# tinyPipes_v2_6.net
KiCad netlist of a schematic drawn in EAGLE
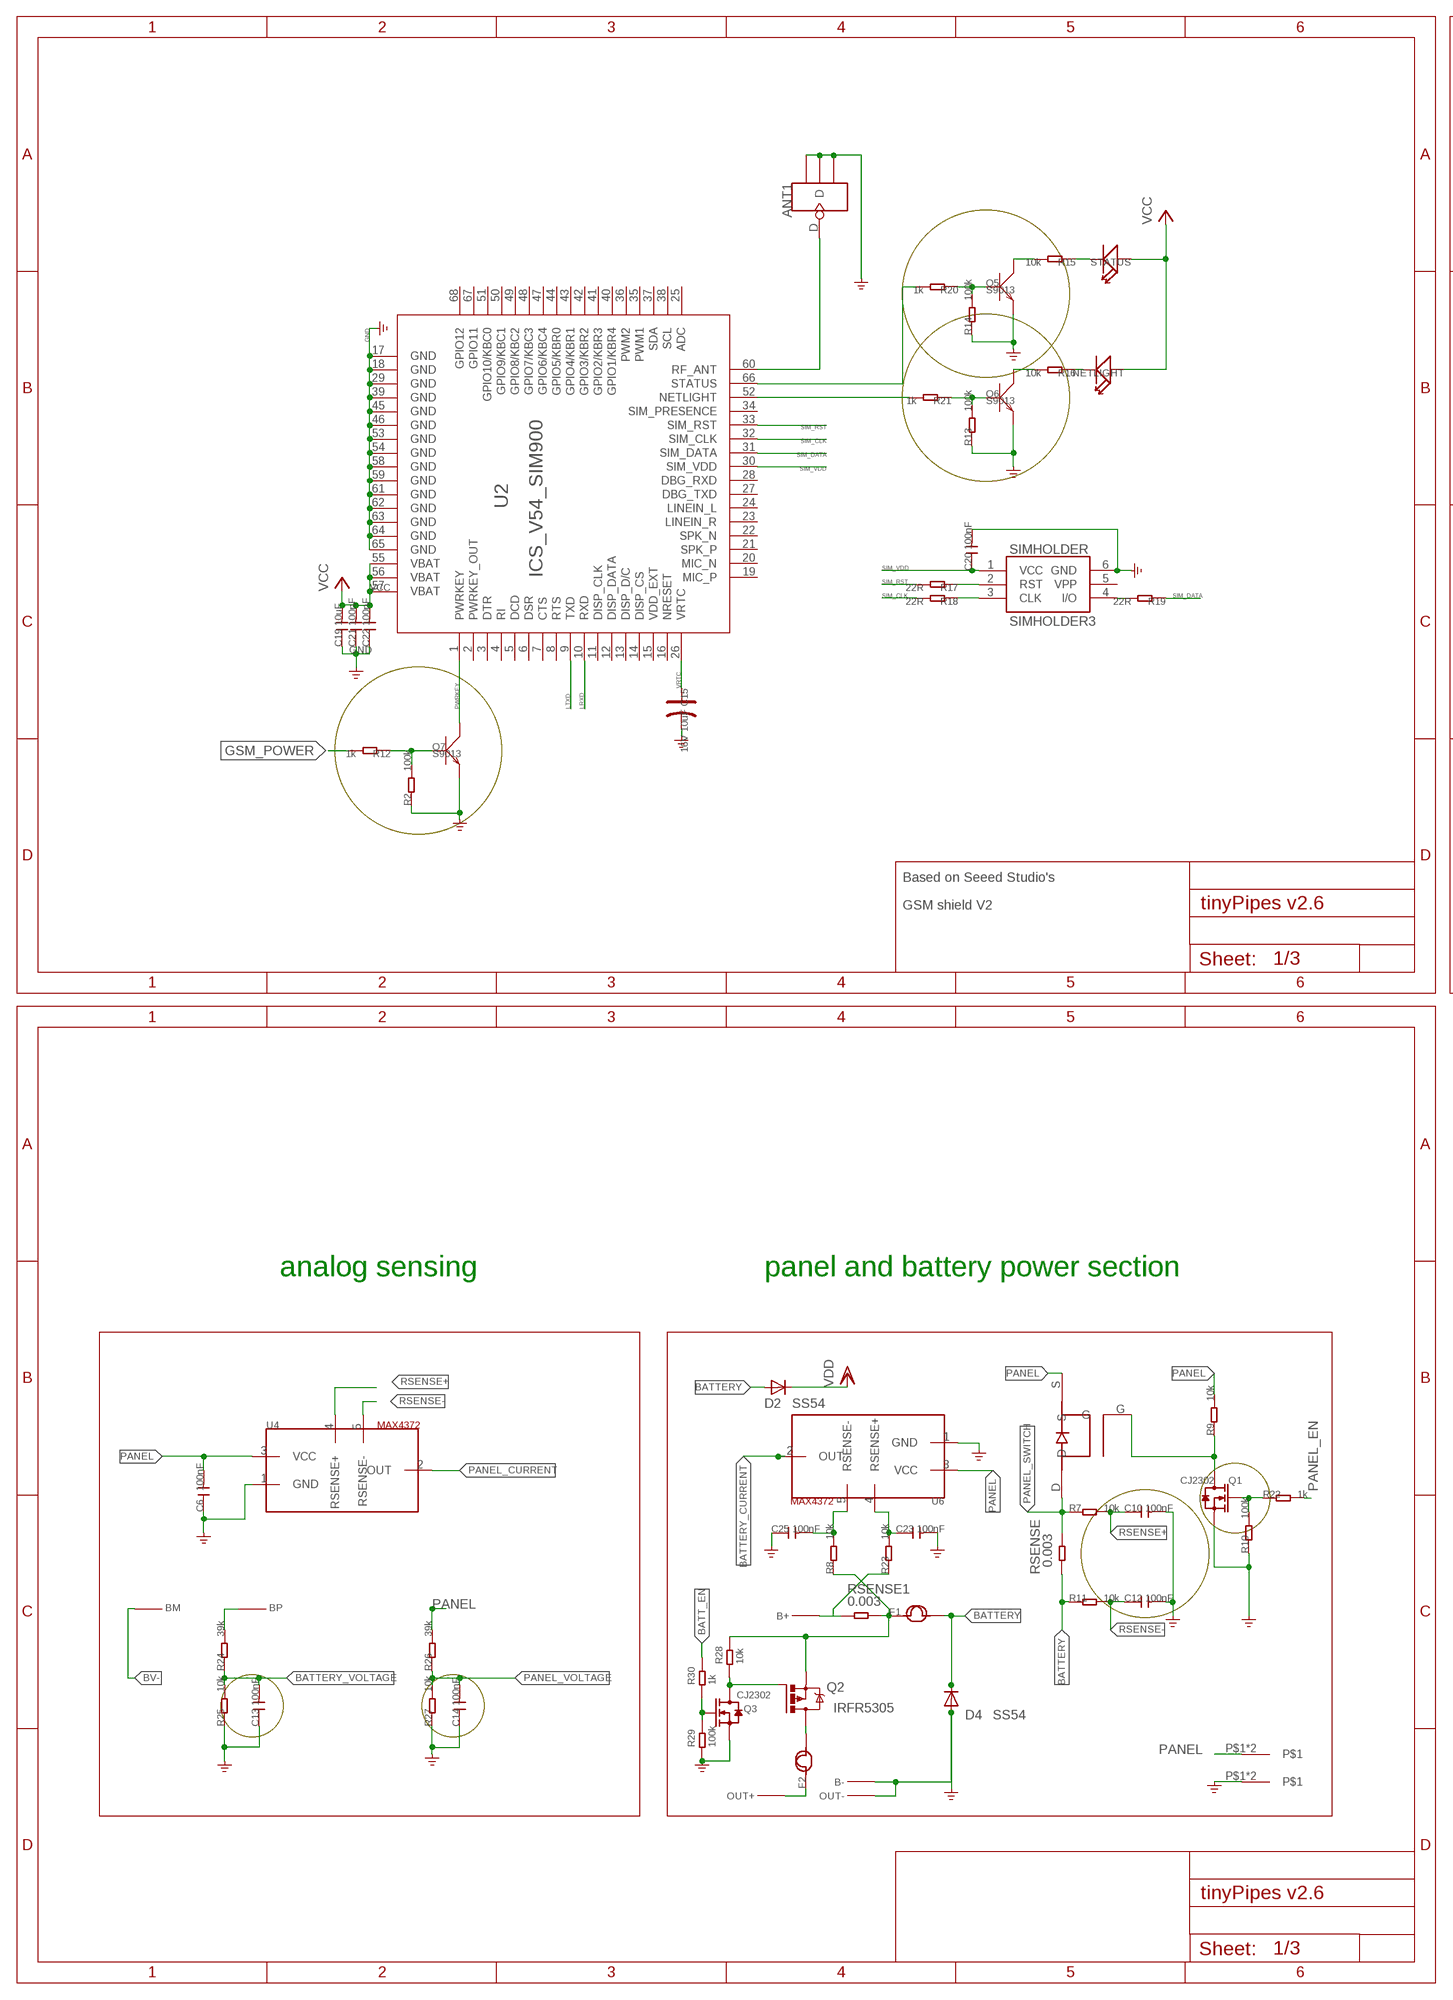
[diagram p0: schematic, sheet 1, part 1 of 2]
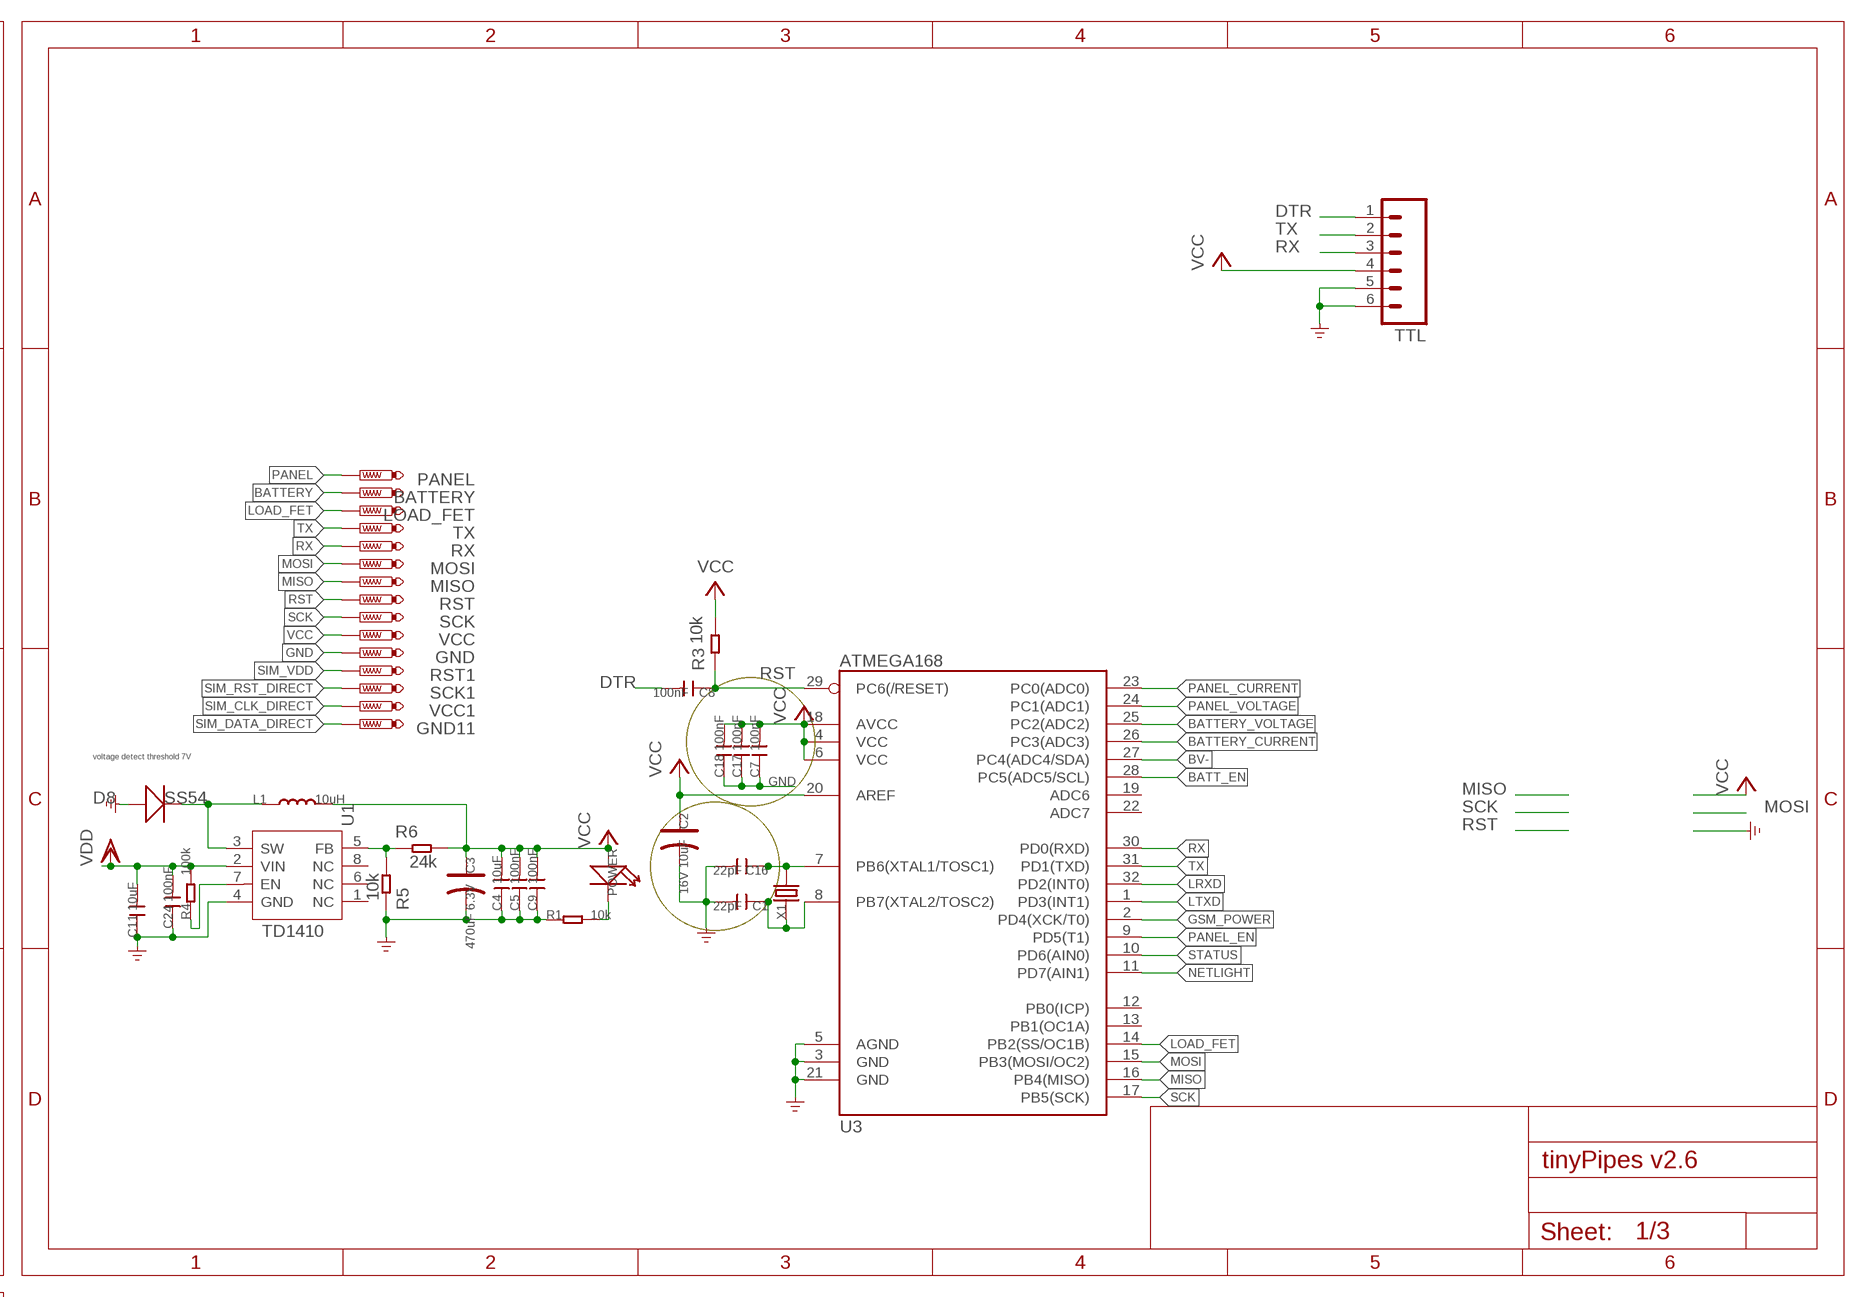
[diagram p1: schematic, sheet 1, part 2 of 2]

(export (version "E")
  (design (tool "Eeschema 10.0.6"))
  (components
    (comp (ref "ANT1")
      (value "ANTENNA-U-FL")
      (footprint "eagle-import:4P-U-FL")
      (libsource (lib "eagle-import") (part "ANTENNA-U-FL"))
    )
    (comp (ref "B+")
      (value "TINYPIPES_BATTBATT")
      (footprint "eagle-import:TINYPIPES_BATT")
      (libsource (lib "eagle-import") (part "TINYPIPES_BATTBATT"))
    )
    (comp (ref "B-")
      (value "TINYPIPES_BATTBATT")
      (footprint "eagle-import:TINYPIPES_BATT")
      (libsource (lib "eagle-import") (part "TINYPIPES_BATTBATT"))
    )
    (comp (ref "BATTERY")
      (value "PTR1B2,54")
      (footprint "eagle-import:B2,54")
      (libsource (lib "eagle-import") (part "PTR1B2,54"))
    )
    (comp (ref "BM")
      (value "TINYPIPES_BATTSBATT")
      (footprint "eagle-import:TINYPIPES_SBATT")
      (libsource (lib "eagle-import") (part "TINYPIPES_BATTSBATT"))
    )
    (comp (ref "BP")
      (value "TINYPIPES_BATTSBATT")
      (footprint "eagle-import:TINYPIPES_SBATT")
      (libsource (lib "eagle-import") (part "TINYPIPES_BATTSBATT"))
    )
    (comp (ref "C1")
      (value "22pF")
      (footprint "eagle-import:C0603")
      (libsource (lib "eagle-import") (part "C-0603"))
    )
    (comp (ref "C2")
      (value "16V 10uF")
      (footprint "eagle-import:AVX-A")
      (libsource (lib "eagle-import") (part "CAP-AVX-A"))
    )
    (comp (ref "C3")
      (value "470uF 6.3V")
      (footprint "eagle-import:AVX-D")
      (libsource (lib "eagle-import") (part "CAP-AVX-D"))
    )
    (comp (ref "C4")
      (value "10uF")
      (footprint "eagle-import:C0805")
      (libsource (lib "eagle-import") (part "C-0805"))
    )
    (comp (ref "C5")
      (value "100nF")
      (footprint "eagle-import:C0603")
      (libsource (lib "eagle-import") (part "C-0603"))
    )
    (comp (ref "C6")
      (value "100nF")
      (footprint "eagle-import:C0603")
      (libsource (lib "eagle-import") (part "C-0603"))
    )
    (comp (ref "C7")
      (value "100nF")
      (footprint "eagle-import:C0603")
      (libsource (lib "eagle-import") (part "C-0603"))
    )
    (comp (ref "C8")
      (value "100nF")
      (footprint "eagle-import:C0603")
      (libsource (lib "eagle-import") (part "C-0603"))
    )
    (comp (ref "C9")
      (value "100nF")
      (footprint "eagle-import:C0603")
      (libsource (lib "eagle-import") (part "C-0603"))
    )
    (comp (ref "C10")
      (value "100nF")
      (footprint "eagle-import:C0805")
      (libsource (lib "eagle-import") (part "C-0805"))
    )
    (comp (ref "C11")
      (value "10uF")
      (footprint "eagle-import:C0805")
      (libsource (lib "eagle-import") (part "C-0805"))
    )
    (comp (ref "C12")
      (value "100nF")
      (footprint "eagle-import:C0805")
      (libsource (lib "eagle-import") (part "C-0805"))
    )
    (comp (ref "C13")
      (value "100nF")
      (footprint "eagle-import:C0603")
      (libsource (lib "eagle-import") (part "C-0603"))
    )
    (comp (ref "C14")
      (value "100nF")
      (footprint "eagle-import:C0603")
      (libsource (lib "eagle-import") (part "C-0603"))
    )
    (comp (ref "C15")
      (value "16V 10uF")
      (footprint "eagle-import:AVX-A")
      (libsource (lib "eagle-import") (part "CAP-AVX-A"))
    )
    (comp (ref "C16")
      (value "22pF")
      (footprint "eagle-import:C0603")
      (libsource (lib "eagle-import") (part "C-0603"))
    )
    (comp (ref "C17")
      (value "100nF")
      (footprint "eagle-import:C0603")
      (libsource (lib "eagle-import") (part "C-0603"))
    )
    (comp (ref "C18")
      (value "100nF")
      (footprint "eagle-import:C0603")
      (libsource (lib "eagle-import") (part "C-0603"))
    )
    (comp (ref "C19")
      (value "10uF")
      (footprint "eagle-import:C0805")
      (libsource (lib "eagle-import") (part "C-0805"))
    )
    (comp (ref "C20")
      (value "100nF")
      (footprint "eagle-import:C0603")
      (libsource (lib "eagle-import") (part "C-0603"))
    )
    (comp (ref "C21")
      (value "100nF")
      (footprint "eagle-import:C0603")
      (libsource (lib "eagle-import") (part "C-0603"))
    )
    (comp (ref "C22")
      (value "100nF")
      (footprint "eagle-import:C0603")
      (libsource (lib "eagle-import") (part "C-0603"))
    )
    (comp (ref "C23")
      (value "100nF")
      (footprint "eagle-import:C0805")
      (libsource (lib "eagle-import") (part "C-0805"))
    )
    (comp (ref "C24")
      (value "100nF")
      (footprint "eagle-import:C0603")
      (libsource (lib "eagle-import") (part "C-0603"))
    )
    (comp (ref "C25")
      (value "100nF")
      (footprint "eagle-import:C0805")
      (libsource (lib "eagle-import") (part "C-0805"))
    )
    (comp (ref "D2")
      (value "SS54")
      (footprint "eagle-import:SMB")
      (libsource (lib "eagle-import") (part "DIODE-SMB"))
    )
    (comp (ref "D4")
      (value "SS54")
      (footprint "eagle-import:SMB")
      (libsource (lib "eagle-import") (part "DIODE-SMB"))
    )
    (comp (ref "D8")
      (value "SS54")
      (footprint "eagle-import:SMB")
      (libsource (lib "eagle-import") (part "D'MBRS240LT3'"))
    )
    (comp (ref "F1")
      (value "FUSE16R700")
      (footprint "eagle-import:0210")
      (libsource (lib "eagle-import") (part "FUSE16R700"))
    )
    (comp (ref "F2")
      (value "FUSE16R700")
      (footprint "eagle-import:0210")
      (libsource (lib "eagle-import") (part "FUSE16R700"))
    )
    (comp (ref "GND")
      (value "PTR1B2,54")
      (footprint "eagle-import:B2,54")
      (libsource (lib "eagle-import") (part "PTR1B2,54"))
    )
    (comp (ref "GND11")
      (value "PTR1B2,54")
      (footprint "eagle-import:B2,54")
      (libsource (lib "eagle-import") (part "PTR1B2,54"))
    )
    (comp (ref "L1")
      (value "10uH")
      (footprint "eagle-import:L0630")
      (libsource (lib "eagle-import") (part "L'0630'"))
    )
    (comp (ref "LOAD_FET")
      (value "PTR1B2,54")
      (footprint "eagle-import:B2,54")
      (libsource (lib "eagle-import") (part "PTR1B2,54"))
    )
    (comp (ref "MISO")
      (value "PTR1B2,54")
      (footprint "eagle-import:B2,54")
      (libsource (lib "eagle-import") (part "PTR1B2,54"))
    )
    (comp (ref "MOSI")
      (value "PTR1B2,54")
      (footprint "eagle-import:B2,54")
      (libsource (lib "eagle-import") (part "PTR1B2,54"))
    )
    (comp (ref "NETLIGHT")
      (value "LED'0603'")
      (footprint "eagle-import:LED-0603")
      (libsource (lib "eagle-import") (part "LED'0603'"))
    )
    (comp (ref "OUT+")
      (value "TINYPIPES_BATTBATT")
      (footprint "eagle-import:TINYPIPES_BATT")
      (libsource (lib "eagle-import") (part "TINYPIPES_BATTBATT"))
    )
    (comp (ref "OUT-")
      (value "TINYPIPES_BATTBATT")
      (footprint "eagle-import:TINYPIPES_BATT")
      (libsource (lib "eagle-import") (part "TINYPIPES_BATTBATT"))
    )
    (comp (ref "PANEL")
      (value "PTR1B2,54")
      (footprint "eagle-import:B2,54")
      (libsource (lib "eagle-import") (part "PTR1B2,54"))
    )
    (comp (ref "PANEL+")
      (value "TINYPIPES_BATTPANEL")
      (footprint "eagle-import:TINYPIPES_PANEL")
      (libsource (lib "eagle-import") (part "tinyPipes_v2.5_TINYPIPES_BATTPANEL"))
    )
    (comp (ref "PANEL-")
      (value "TINYPIPES_BATTPANEL")
      (footprint "eagle-import:TINYPIPES_PANEL")
      (libsource (lib "eagle-import") (part "tinyPipes_v2.5_TINYPIPES_BATTPANEL"))
    )
    (comp (ref "POWER")
      (value "LED'0603'")
      (footprint "eagle-import:LED-0603")
      (libsource (lib "eagle-import") (part "LED'0603'"))
    )
    (comp (ref "Q1")
      (value "CJ2302")
      (footprint "eagle-import:SOT23")
      (libsource (lib "eagle-import") (part "MOSFET-N'SOT23'"))
    )
    (comp (ref "Q2")
      (value "IRFR5305")
      (footprint "eagle-import:D-PAK_TO252AA")
      (libsource (lib "eagle-import") (part "IRF?5305R"))
    )
    (comp (ref "Q3")
      (value "CJ2302")
      (footprint "eagle-import:SOT23")
      (libsource (lib "eagle-import") (part "MOSFET-N'SOT23'"))
    )
    (comp (ref "Q5")
      (value "S9013")
      (footprint "eagle-import:SOT23")
      (libsource (lib "eagle-import") (part "TRANSISTOR-NPN-SOT23"))
    )
    (comp (ref "Q6")
      (value "S9013")
      (footprint "eagle-import:SOT23")
      (libsource (lib "eagle-import") (part "TRANSISTOR-NPN-SOT23"))
    )
    (comp (ref "Q7")
      (value "S9013")
      (footprint "eagle-import:SOT23")
      (libsource (lib "eagle-import") (part "TRANSISTOR-NPN-SOT23"))
    )
    (comp (ref "R1")
      (value "10k")
      (footprint "eagle-import:R0603")
      (libsource (lib "eagle-import") (part "R-0603"))
    )
    (comp (ref "R2")
      (value "100k")
      (footprint "eagle-import:R0603")
      (libsource (lib "eagle-import") (part "R-0603"))
    )
    (comp (ref "R3")
      (value "10k")
      (footprint "eagle-import:R0603")
      (libsource (lib "eagle-import") (part "R-0603"))
    )
    (comp (ref "R4")
      (value "100k")
      (footprint "eagle-import:R0603")
      (libsource (lib "eagle-import") (part "R-0603"))
    )
    (comp (ref "R5")
      (value "10k")
      (footprint "eagle-import:R0603")
      (libsource (lib "eagle-import") (part "R-0603"))
    )
    (comp (ref "R6")
      (value "24k")
      (footprint "eagle-import:R0603")
      (libsource (lib "eagle-import") (part "R-0603"))
    )
    (comp (ref "R7")
      (value "10k")
      (footprint "eagle-import:R0603")
      (libsource (lib "eagle-import") (part "R-0603"))
    )
    (comp (ref "R8")
      (value "10k")
      (footprint "eagle-import:R0603")
      (libsource (lib "eagle-import") (part "R-0603"))
    )
    (comp (ref "R9")
      (value "10k")
      (footprint "eagle-import:R0603")
      (libsource (lib "eagle-import") (part "R-0603"))
    )
    (comp (ref "R10")
      (value "100k")
      (footprint "eagle-import:R0603")
      (libsource (lib "eagle-import") (part "R-0603"))
    )
    (comp (ref "R11")
      (value "10k")
      (footprint "eagle-import:R0603")
      (libsource (lib "eagle-import") (part "R-0603"))
    )
    (comp (ref "R12")
      (value "1k")
      (footprint "eagle-import:R0603")
      (libsource (lib "eagle-import") (part "R-0603"))
    )
    (comp (ref "R13")
      (value "100k")
      (footprint "eagle-import:R0603")
      (libsource (lib "eagle-import") (part "R-0603"))
    )
    (comp (ref "R14")
      (value "100k")
      (footprint "eagle-import:R0603")
      (libsource (lib "eagle-import") (part "R-0603"))
    )
    (comp (ref "R15")
      (value "10k")
      (footprint "eagle-import:R0603")
      (libsource (lib "eagle-import") (part "R-0603"))
    )
    (comp (ref "R16")
      (value "10k")
      (footprint "eagle-import:R0603")
      (libsource (lib "eagle-import") (part "R-0603"))
    )
    (comp (ref "R17")
      (value "22R")
      (footprint "eagle-import:R0603")
      (libsource (lib "eagle-import") (part "R-0603"))
    )
    (comp (ref "R18")
      (value "22R")
      (footprint "eagle-import:R0603")
      (libsource (lib "eagle-import") (part "R-0603"))
    )
    (comp (ref "R19")
      (value "22R")
      (footprint "eagle-import:R0603")
      (libsource (lib "eagle-import") (part "R-0603"))
    )
    (comp (ref "R20")
      (value "1k")
      (footprint "eagle-import:R0603")
      (libsource (lib "eagle-import") (part "R-0603"))
    )
    (comp (ref "R21")
      (value "1k")
      (footprint "eagle-import:R0603")
      (libsource (lib "eagle-import") (part "R-0603"))
    )
    (comp (ref "R22")
      (value "1k")
      (footprint "eagle-import:R0603")
      (libsource (lib "eagle-import") (part "R-0603"))
    )
    (comp (ref "R23")
      (value "10k")
      (footprint "eagle-import:R0603")
      (libsource (lib "eagle-import") (part "R-0603"))
    )
    (comp (ref "R24")
      (value "39k")
      (footprint "eagle-import:R0603")
      (libsource (lib "eagle-import") (part "R-0603"))
    )
    (comp (ref "R25")
      (value "10k")
      (footprint "eagle-import:R0603")
      (libsource (lib "eagle-import") (part "R-0603"))
    )
    (comp (ref "R26")
      (value "39k")
      (footprint "eagle-import:R0603")
      (libsource (lib "eagle-import") (part "R-0603"))
    )
    (comp (ref "R27")
      (value "10k")
      (footprint "eagle-import:R0603")
      (libsource (lib "eagle-import") (part "R-0603"))
    )
    (comp (ref "R28")
      (value "10k")
      (footprint "eagle-import:R0603")
      (libsource (lib "eagle-import") (part "R-0603"))
    )
    (comp (ref "R29")
      (value "100k")
      (footprint "eagle-import:R0603")
      (libsource (lib "eagle-import") (part "R-0603"))
    )
    (comp (ref "R30")
      (value "1k")
      (footprint "eagle-import:R0603")
      (libsource (lib "eagle-import") (part "R-0603"))
    )
    (comp (ref "RSENSE")
      (value "0.003")
      (footprint "eagle-import:R2512")
      (libsource (lib "eagle-import") (part "R-2512"))
    )
    (comp (ref "RSENSE1")
      (value "0.003")
      (footprint "eagle-import:R2512")
      (libsource (lib "eagle-import") (part "R-2512"))
    )
    (comp (ref "RST")
      (value "PTR1B2,54")
      (footprint "eagle-import:B2,54")
      (libsource (lib "eagle-import") (part "PTR1B2,54"))
    )
    (comp (ref "RST1")
      (value "PTR1B2,54")
      (footprint "eagle-import:B2,54")
      (libsource (lib "eagle-import") (part "PTR1B2,54"))
    )
    (comp (ref "RX")
      (value "PTR1B2,54")
      (footprint "eagle-import:B2,54")
      (libsource (lib "eagle-import") (part "PTR1B2,54"))
    )
    (comp (ref "SCK")
      (value "PTR1B2,54")
      (footprint "eagle-import:B2,54")
      (libsource (lib "eagle-import") (part "PTR1B2,54"))
    )
    (comp (ref "SCK1")
      (value "PTR1B2,54")
      (footprint "eagle-import:B2,54")
      (libsource (lib "eagle-import") (part "PTR1B2,54"))
    )
    (comp (ref "SIMHOLDER")
      (value "SIMHOLDER3")
      (footprint "eagle-import:SIMHOLDER3")
      (libsource (lib "eagle-import") (part "SIMHOLDER3"))
    )
    (comp (ref "STATUS")
      (value "LED'0603'")
      (footprint "eagle-import:LED-0603")
      (libsource (lib "eagle-import") (part "LED'0603'"))
    )
    (comp (ref "TTL")
      (value "M06LOCK")
      (footprint "eagle-import:1X06_LOCK")
      (libsource (lib "eagle-import") (part "M06LOCK"))
    )
    (comp (ref "TX")
      (value "PTR1B2,54")
      (footprint "eagle-import:B2,54")
      (libsource (lib "eagle-import") (part "PTR1B2,54"))
    )
    (comp (ref "U1")
      (value "TD1410")
      (footprint "eagle-import:SOP8")
      (libsource (lib "eagle-import") (part "TD1410"))
    )
    (comp (ref "U2")
      (value "ICS_V54_SIM900")
      (footprint "eagle-import:ICS_V54_SIM900")
      (libsource (lib "eagle-import") (part "ICS_V54_SIM900"))
    )
    (comp (ref "U3")
      (value "ATMEGA168")
      (footprint "eagle-import:TQFP32-08")
      (libsource (lib "eagle-import") (part "ATMEGA168"))
    )
    (comp (ref "U4")
      (value "MAX4372")
      (footprint "eagle-import:SOT23-5")
      (libsource (lib "eagle-import") (part "MAX4372"))
    )
    (comp (ref "U5")
      (value "SI4435POWER")
      (footprint "eagle-import:SO8_FET")
      (libsource (lib "eagle-import") (part "SI4435POWER"))
    )
    (comp (ref "U6")
      (value "MAX4372")
      (footprint "eagle-import:SOT23-5")
      (libsource (lib "eagle-import") (part "MAX4372"))
    )
    (comp (ref "VCC")
      (value "PTR1B2,54")
      (footprint "eagle-import:B2,54")
      (libsource (lib "eagle-import") (part "PTR1B2,54"))
    )
    (comp (ref "VCC1")
      (value "PTR1B2,54")
      (footprint "eagle-import:B2,54")
      (libsource (lib "eagle-import") (part "PTR1B2,54"))
    )
    (comp (ref "X1")
      (value "CRYSTAL'5032'")
      (footprint "eagle-import:2P-SMD-5X3.2")
      (libsource (lib "eagle-import") (part "CRYSTAL'5032'"))
    )
  )
  (nets
    (net (code "1") (name "BATTERY") (class "Default")
      (node (ref "BATTERY") (pin "TP") (pinfunction "TP_TP") (pintype "input"))
      (node (ref "D2") (pin "A") (pinfunction "A_A") (pintype "passive"))
      (node (ref "D4") (pin "C") (pinfunction "C_C") (pintype "passive"))
      (node (ref "F1") (pin "2") (pinfunction "2_2") (pintype "bidirectional"))
      (node (ref "R11") (pin "1") (pinfunction "1_1") (pintype "passive"))
      (node (ref "RSENSE") (pin "1") (pinfunction "1_1") (pintype "passive"))
    )
    (net (code "2") (name "BATTERY_CURRENT") (class "Default")
      (node (ref "U3") (pin "26") (pinfunction "PC3(ADC3)_26") (pintype "bidirectional"))
      (node (ref "U6") (pin "2") (pinfunction "OUT_2") (pintype "bidirectional"))
    )
    (net (code "3") (name "BATTERY_VOLTAGE") (class "Default")
      (node (ref "C13") (pin "2") (pinfunction "2_2") (pintype "passive"))
      (node (ref "R24") (pin "1") (pinfunction "1_1") (pintype "passive"))
      (node (ref "R25") (pin "2") (pinfunction "2_2") (pintype "passive"))
      (node (ref "U3") (pin "25") (pinfunction "PC2(ADC2)_25") (pintype "bidirectional"))
    )
    (net (code "4") (name "BATT_EN") (class "Default")
      (node (ref "R30") (pin "2") (pinfunction "2_2") (pintype "passive"))
      (node (ref "U3") (pin "28") (pinfunction "PC5(ADC5/SCL)_28") (pintype "bidirectional"))
    )
    (net (code "5") (name "BV-") (class "Default")
      (node (ref "BM") (pin "P$1") (pinfunction "P$1_P$1") (pintype "bidirectional"))
      (node (ref "U3") (pin "27") (pinfunction "PC4(ADC4/SDA)_27") (pintype "bidirectional"))
    )
    (net (code "6") (name "DTR") (class "Default")
      (node (ref "C8") (pin "2") (pinfunction "2_2") (pintype "passive"))
      (node (ref "TTL") (pin "1") (pinfunction "1_1") (pintype "passive"))
    )
    (net (code "7") (name "GND") (class "Default")
      (node (ref "ANT1") (pin "GND1") (pinfunction "GND1_GND1") (pintype "bidirectional"))
      (node (ref "ANT1") (pin "GND2") (pinfunction "GND2_GND2") (pintype "bidirectional"))
      (node (ref "ANT1") (pin "GND3") (pinfunction "GND3_GND3") (pintype "bidirectional"))
      (node (ref "B-") (pin "1") (pinfunction "P$1_1") (pintype "bidirectional"))
      (node (ref "C1") (pin "2") (pinfunction "2_2") (pintype "passive"))
      (node (ref "C10") (pin "2") (pinfunction "2_2") (pintype "passive"))
      (node (ref "C11") (pin "1") (pinfunction "1_1") (pintype "passive"))
      (node (ref "C12") (pin "2") (pinfunction "2_2") (pintype "passive"))
      (node (ref "C13") (pin "1") (pinfunction "1_1") (pintype "passive"))
      (node (ref "C14") (pin "1") (pinfunction "1_1") (pintype "passive"))
      (node (ref "C15") (pin "-") (pinfunction "-_-") (pintype "passive"))
      (node (ref "C16") (pin "2") (pinfunction "2_2") (pintype "passive"))
      (node (ref "C17") (pin "1") (pinfunction "1_1") (pintype "passive"))
      (node (ref "C18") (pin "1") (pinfunction "1_1") (pintype "passive"))
      (node (ref "C19") (pin "1") (pinfunction "1_1") (pintype "passive"))
      (node (ref "C2") (pin "-") (pinfunction "-_-") (pintype "passive"))
      (node (ref "C20") (pin "2") (pinfunction "2_2") (pintype "passive"))
      (node (ref "C21") (pin "1") (pinfunction "1_1") (pintype "passive"))
      (node (ref "C22") (pin "1") (pinfunction "1_1") (pintype "passive"))
      (node (ref "C23") (pin "2") (pinfunction "2_2") (pintype "passive"))
      (node (ref "C24") (pin "1") (pinfunction "1_1") (pintype "passive"))
      (node (ref "C25") (pin "1") (pinfunction "1_1") (pintype "passive"))
      (node (ref "C3") (pin "-") (pinfunction "-_-") (pintype "passive"))
      (node (ref "C4") (pin "1") (pinfunction "1_1") (pintype "passive"))
      (node (ref "C5") (pin "1") (pinfunction "1_1") (pintype "passive"))
      (node (ref "C6") (pin "1") (pinfunction "1_1") (pintype "passive"))
      (node (ref "C7") (pin "1") (pinfunction "1_1") (pintype "passive"))
      (node (ref "C9") (pin "1") (pinfunction "1_1") (pintype "passive"))
      (node (ref "D4") (pin "A") (pinfunction "A_A") (pintype "passive"))
      (node (ref "D8") (pin "+") (pinfunction "+_+") (pintype "passive"))
      (node (ref "GND") (pin "TP") (pinfunction "TP_TP") (pintype "input"))
      (node (ref "OUT-") (pin "1") (pinfunction "P$1_1") (pintype "bidirectional"))
      (node (ref "PANEL-") (pin "P$1") (pinfunction "P$1_P$1") (pintype "bidirectional"))
      (node (ref "PANEL-") (pin "P$2") (pinfunction "P$1_P$2") (pintype "bidirectional"))
      (node (ref "Q1") (pin "2") (pinfunction "S_2") (pintype "passive"))
      (node (ref "Q3") (pin "2") (pinfunction "S_2") (pintype "passive"))
      (node (ref "Q5") (pin "2") (pinfunction "E_2") (pintype "passive"))
      (node (ref "Q6") (pin "2") (pinfunction "E_2") (pintype "passive"))
      (node (ref "Q7") (pin "2") (pinfunction "E_2") (pintype "passive"))
      (node (ref "R1") (pin "1") (pinfunction "1_1") (pintype "passive"))
      (node (ref "R10") (pin "1") (pinfunction "1_1") (pintype "passive"))
      (node (ref "R13") (pin "1") (pinfunction "1_1") (pintype "passive"))
      (node (ref "R14") (pin "1") (pinfunction "1_1") (pintype "passive"))
      (node (ref "R2") (pin "1") (pinfunction "1_1") (pintype "passive"))
      (node (ref "R25") (pin "1") (pinfunction "1_1") (pintype "passive"))
      (node (ref "R27") (pin "1") (pinfunction "1_1") (pintype "passive"))
      (node (ref "R29") (pin "1") (pinfunction "1_1") (pintype "passive"))
      (node (ref "R5") (pin "2") (pinfunction "2_2") (pintype "passive"))
      (node (ref "SIMHOLDER") (pin "6") (pinfunction "GND_6") (pintype "bidirectional"))
      (node (ref "TTL") (pin "5") (pinfunction "5_5") (pintype "passive"))
      (node (ref "TTL") (pin "6") (pinfunction "6_6") (pintype "passive"))
      (node (ref "U1") (pin "4") (pinfunction "GND_4") (pintype "power_in"))
      (node (ref "U2") (pin "17") (pinfunction "GND_17") (pintype "power_in"))
      (node (ref "U2") (pin "18") (pinfunction "GND_18") (pintype "power_in"))
      (node (ref "U2") (pin "29") (pinfunction "GND_29") (pintype "power_in"))
      (node (ref "U2") (pin "39") (pinfunction "GND_39") (pintype "power_in"))
      (node (ref "U2") (pin "45") (pinfunction "GND_45") (pintype "power_in"))
      (node (ref "U2") (pin "46") (pinfunction "GND_46") (pintype "power_in"))
      (node (ref "U2") (pin "53") (pinfunction "GND_53") (pintype "power_in"))
      (node (ref "U2") (pin "54") (pinfunction "GND_54") (pintype "power_in"))
      (node (ref "U2") (pin "58") (pinfunction "GND_58") (pintype "power_in"))
      (node (ref "U2") (pin "59") (pinfunction "GND_59") (pintype "power_in"))
      (node (ref "U2") (pin "61") (pinfunction "GND_61") (pintype "power_in"))
      (node (ref "U2") (pin "62") (pinfunction "GND_62") (pintype "power_in"))
      (node (ref "U2") (pin "63") (pinfunction "GND_63") (pintype "power_in"))
      (node (ref "U2") (pin "64") (pinfunction "GND_64") (pintype "power_in"))
      (node (ref "U2") (pin "65") (pinfunction "GND_65") (pintype "power_in"))
      (node (ref "U3") (pin "21") (pinfunction "GND_21") (pintype "bidirectional"))
      (node (ref "U3") (pin "3") (pinfunction "GND_3") (pintype "bidirectional"))
      (node (ref "U3") (pin "5") (pinfunction "AGND_5") (pintype "bidirectional"))
      (node (ref "U4") (pin "1") (pinfunction "GND_1") (pintype "bidirectional"))
      (node (ref "U6") (pin "1") (pinfunction "GND_1") (pintype "bidirectional"))
    )
    (net (code "8") (name "GSM_POWER") (class "Default")
      (node (ref "R12") (pin "2") (pinfunction "2_2") (pintype "passive"))
      (node (ref "U3") (pin "2") (pinfunction "PD4(XCK/T0)_2") (pintype "bidirectional"))
    )
    (net (code "9") (name "LOAD_FET") (class "Default")
      (node (ref "LOAD_FET") (pin "TP") (pinfunction "TP_TP") (pintype "input"))
      (node (ref "U3") (pin "14") (pinfunction "PB2(SS/OC1B)_14") (pintype "bidirectional"))
    )
    (net (code "10") (name "LRXD") (class "Default")
      (node (ref "U2") (pin "10") (pinfunction "RXD_10") (pintype "input"))
      (node (ref "U3") (pin "32") (pinfunction "PD2(INT0)_32") (pintype "bidirectional"))
    )
    (net (code "11") (name "LTXD") (class "Default")
      (node (ref "U2") (pin "9") (pinfunction "TXD_9") (pintype "output"))
      (node (ref "U3") (pin "1") (pinfunction "PD3(INT1)_1") (pintype "bidirectional"))
    )
    (net (code "12") (name "MISO") (class "Default")
      (node (ref "MISO") (pin "TP") (pinfunction "TP_TP") (pintype "input"))
      (node (ref "U3") (pin "16") (pinfunction "PB4(MISO)_16") (pintype "bidirectional"))
    )
    (net (code "13") (name "MOSI") (class "Default")
      (node (ref "MOSI") (pin "TP") (pinfunction "TP_TP") (pintype "input"))
      (node (ref "U3") (pin "15") (pinfunction "PB3(MOSI/OC2)_15") (pintype "bidirectional"))
    )
    (net (code "14") (name "NETLIGHT") (class "Default")
      (node (ref "R21") (pin "2") (pinfunction "2_2") (pintype "passive"))
      (node (ref "U2") (pin "52") (pinfunction "NETLIGHT_52") (pintype "output"))
      (node (ref "U3") (pin "11") (pinfunction "PD7(AIN1)_11") (pintype "bidirectional"))
    )
    (net (code "15") (name "Net-(B+-P$1)") (class "Default")
      (node (ref "B+") (pin "1") (pinfunction "P$1_1") (pintype "bidirectional"))
      (node (ref "R23") (pin "1") (pinfunction "1_1") (pintype "passive"))
      (node (ref "RSENSE1") (pin "1") (pinfunction "1_1") (pintype "passive"))
    )
    (net (code "16") (name "Net-(BP-PadP$1)") (class "Default")
      (node (ref "BP") (pin "P$1") (pinfunction "P$1_P$1") (pintype "bidirectional"))
      (node (ref "R24") (pin "2") (pinfunction "2_2") (pintype "passive"))
    )
    (net (code "17") (name "Net-(NETLIGHT-Pad-)") (class "Default")
      (node (ref "NETLIGHT") (pin "-") (pinfunction "-_-") (pintype "passive"))
      (node (ref "R16") (pin "1") (pinfunction "1_1") (pintype "passive"))
    )
    (net (code "18") (name "Net-(OUT+-P$1)") (class "Default")
      (node (ref "F2") (pin "1") (pinfunction "1_1") (pintype "bidirectional"))
      (node (ref "OUT+") (pin "1") (pinfunction "P$1_1") (pintype "bidirectional"))
    )
    (net (code "19") (name "Net-(POWER-Pad-)") (class "Default")
      (node (ref "POWER") (pin "-") (pinfunction "-_-") (pintype "passive"))
      (node (ref "R1") (pin "2") (pinfunction "2_2") (pintype "passive"))
    )
    (net (code "20") (name "Net-(Q1-D)") (class "Default")
      (node (ref "Q1") (pin "3") (pinfunction "D_3") (pintype "passive"))
      (node (ref "R9") (pin "1") (pinfunction "1_1") (pintype "passive"))
      (node (ref "U5") (pin "G") (pinfunction "G_G") (pintype "bidirectional"))
    )
    (net (code "21") (name "Net-(Q1-G)") (class "Default")
      (node (ref "Q1") (pin "1") (pinfunction "G_1") (pintype "passive"))
      (node (ref "R10") (pin "2") (pinfunction "2_2") (pintype "passive"))
      (node (ref "R22") (pin "1") (pinfunction "1_1") (pintype "passive"))
    )
    (net (code "22") (name "Net-(Q2-D)") (class "Default")
      (node (ref "F2") (pin "2") (pinfunction "2_2") (pintype "bidirectional"))
      (node (ref "Q2") (pin "4") (pinfunction "D_4") (pintype "passive"))
    )
    (net (code "23") (name "Net-(Q2-G)") (class "Default")
      (node (ref "Q2") (pin "1") (pinfunction "G_1") (pintype "passive"))
      (node (ref "Q3") (pin "3") (pinfunction "D_3") (pintype "passive"))
      (node (ref "R28") (pin "1") (pinfunction "1_1") (pintype "passive"))
    )
    (net (code "24") (name "Net-(Q2-S)") (class "Default")
      (node (ref "F1") (pin "1") (pinfunction "1_1") (pintype "bidirectional"))
      (node (ref "Q2") (pin "3") (pinfunction "S_3") (pintype "passive"))
      (node (ref "R28") (pin "2") (pinfunction "2_2") (pintype "passive"))
      (node (ref "R8") (pin "1") (pinfunction "1_1") (pintype "passive"))
      (node (ref "RSENSE1") (pin "2") (pinfunction "2_2") (pintype "passive"))
    )
    (net (code "25") (name "Net-(Q3-G)") (class "Default")
      (node (ref "Q3") (pin "1") (pinfunction "G_1") (pintype "passive"))
      (node (ref "R29") (pin "2") (pinfunction "2_2") (pintype "passive"))
      (node (ref "R30") (pin "1") (pinfunction "1_1") (pintype "passive"))
    )
    (net (code "26") (name "Net-(Q5-B)") (class "Default")
      (node (ref "Q5") (pin "1") (pinfunction "B_1") (pintype "passive"))
      (node (ref "R14") (pin "2") (pinfunction "2_2") (pintype "passive"))
      (node (ref "R20") (pin "1") (pinfunction "1_1") (pintype "passive"))
    )
    (net (code "27") (name "Net-(Q5-C)") (class "Default")
      (node (ref "Q5") (pin "3") (pinfunction "C_3") (pintype "passive"))
      (node (ref "R15") (pin "2") (pinfunction "2_2") (pintype "passive"))
    )
    (net (code "28") (name "Net-(Q6-B)") (class "Default")
      (node (ref "Q6") (pin "1") (pinfunction "B_1") (pintype "passive"))
      (node (ref "R13") (pin "2") (pinfunction "2_2") (pintype "passive"))
      (node (ref "R21") (pin "1") (pinfunction "1_1") (pintype "passive"))
    )
    (net (code "29") (name "Net-(Q6-C)") (class "Default")
      (node (ref "Q6") (pin "3") (pinfunction "C_3") (pintype "passive"))
      (node (ref "R16") (pin "2") (pinfunction "2_2") (pintype "passive"))
    )
    (net (code "30") (name "Net-(Q7-B)") (class "Default")
      (node (ref "Q7") (pin "1") (pinfunction "B_1") (pintype "passive"))
      (node (ref "R12") (pin "1") (pinfunction "1_1") (pintype "passive"))
      (node (ref "R2") (pin "2") (pinfunction "2_2") (pintype "passive"))
    )
    (net (code "31") (name "Net-(R15-Pad1)") (class "Default")
      (node (ref "R15") (pin "1") (pinfunction "1_1") (pintype "passive"))
      (node (ref "STATUS") (pin "-") (pinfunction "-_-") (pintype "passive"))
    )
    (net (code "32") (name "Net-(U1-EN)") (class "Default")
      (node (ref "R4") (pin "1") (pinfunction "1_1") (pintype "passive"))
      (node (ref "U1") (pin "7") (pinfunction "EN_7") (pintype "input"))
    )
    (net (code "33") (name "Net-(U1-FB)") (class "Default")
      (node (ref "R5") (pin "1") (pinfunction "1_1") (pintype "passive"))
      (node (ref "R6") (pin "1") (pinfunction "1_1") (pintype "passive"))
      (node (ref "U1") (pin "5") (pinfunction "FB_5") (pintype "input"))
    )
    (net (code "34") (name "Net-(U1-SW)") (class "Default")
      (node (ref "D8") (pin "-") (pinfunction "-_-") (pintype "passive"))
      (node (ref "L1") (pin "1") (pinfunction "1_1") (pintype "passive"))
      (node (ref "U1") (pin "3") (pinfunction "SW_3") (pintype "output"))
    )
    (net (code "35") (name "Net-(U2-RF_ANT)") (class "Default")
      (node (ref "ANT1") (pin "D") (pinfunction "D_D") (pintype "bidirectional"))
      (node (ref "U2") (pin "60") (pinfunction "RF_ANT_60") (pintype "bidirectional"))
    )
    (net (code "36") (name "Net-(U3-PB6(XTAL1{slash}TOSC1))") (class "Default")
      (node (ref "C16") (pin "1") (pinfunction "1_1") (pintype "passive"))
      (node (ref "U3") (pin "7") (pinfunction "PB6(XTAL1/TOSC1)_7") (pintype "bidirectional"))
      (node (ref "X1") (pin "2") (pinfunction "2_2") (pintype "passive"))
    )
    (net (code "37") (name "Net-(U3-PB7(XTAL2{slash}TOSC2))") (class "Default")
      (node (ref "C1") (pin "1") (pinfunction "1_1") (pintype "passive"))
      (node (ref "U3") (pin "8") (pinfunction "PB7(XTAL2/TOSC2)_8") (pintype "bidirectional"))
      (node (ref "X1") (pin "1") (pinfunction "1_1") (pintype "passive"))
    )
    (net (code "38") (name "Net-(U6-RSENSE+)") (class "Default")
      (node (ref "C23") (pin "1") (pinfunction "1_1") (pintype "passive"))
      (node (ref "R23") (pin "2") (pinfunction "2_2") (pintype "passive"))
      (node (ref "U6") (pin "4") (pinfunction "RSENSE+_4") (pintype "bidirectional"))
    )
    (net (code "39") (name "Net-(U6-RSENSE-)") (class "Default")
      (node (ref "C25") (pin "2") (pinfunction "2_2") (pintype "passive"))
      (node (ref "R8") (pin "2") (pinfunction "2_2") (pintype "passive"))
      (node (ref "U6") (pin "5") (pinfunction "RSENSE-_5") (pintype "bidirectional"))
    )
    (net (code "40") (name "PANEL") (class "Default")
      (node (ref "C6") (pin "2") (pinfunction "2_2") (pintype "passive"))
      (node (ref "PANEL") (pin "TP") (pinfunction "TP_TP") (pintype "input"))
      (node (ref "PANEL+") (pin "P$1") (pinfunction "P$1_P$1") (pintype "bidirectional"))
      (node (ref "PANEL+") (pin "P$2") (pinfunction "P$1_P$2") (pintype "bidirectional"))
      (node (ref "R26") (pin "2") (pinfunction "2_2") (pintype "passive"))
      (node (ref "R9") (pin "2") (pinfunction "2_2") (pintype "passive"))
      (node (ref "U4") (pin "3") (pinfunction "VCC_3") (pintype "bidirectional"))
      (node (ref "U5") (pin "S") (pinfunction "S_S") (pintype "bidirectional"))
      (node (ref "U6") (pin "3") (pinfunction "VCC_3") (pintype "bidirectional"))
    )
    (net (code "41") (name "PANEL_CURRENT") (class "Default")
      (node (ref "U3") (pin "23") (pinfunction "PC0(ADC0)_23") (pintype "bidirectional"))
      (node (ref "U4") (pin "2") (pinfunction "OUT_2") (pintype "bidirectional"))
    )
    (net (code "42") (name "PANEL_EN") (class "Default")
      (node (ref "R22") (pin "2") (pinfunction "2_2") (pintype "passive"))
      (node (ref "U3") (pin "9") (pinfunction "PD5(T1)_9") (pintype "bidirectional"))
    )
    (net (code "43") (name "PANEL_SWITCH") (class "Default")
      (node (ref "R7") (pin "1") (pinfunction "1_1") (pintype "passive"))
      (node (ref "RSENSE") (pin "2") (pinfunction "2_2") (pintype "passive"))
      (node (ref "U5") (pin "D") (pinfunction "D_D") (pintype "bidirectional"))
    )
    (net (code "44") (name "PANEL_VOLTAGE") (class "Default")
      (node (ref "C14") (pin "2") (pinfunction "2_2") (pintype "passive"))
      (node (ref "R26") (pin "1") (pinfunction "1_1") (pintype "passive"))
      (node (ref "R27") (pin "2") (pinfunction "2_2") (pintype "passive"))
      (node (ref "U3") (pin "24") (pinfunction "PC1(ADC1)_24") (pintype "bidirectional"))
    )
    (net (code "45") (name "PWRKEY") (class "Default")
      (node (ref "Q7") (pin "3") (pinfunction "C_3") (pintype "passive"))
      (node (ref "U2") (pin "1") (pinfunction "PWRKEY_1") (pintype "input"))
    )
    (net (code "46") (name "RSENSE+") (class "Default")
      (node (ref "C10") (pin "1") (pinfunction "1_1") (pintype "passive"))
      (node (ref "R7") (pin "2") (pinfunction "2_2") (pintype "passive"))
      (node (ref "U4") (pin "4") (pinfunction "RSENSE+_4") (pintype "bidirectional"))
    )
    (net (code "47") (name "RSENSE-") (class "Default")
      (node (ref "C12") (pin "1") (pinfunction "1_1") (pintype "passive"))
      (node (ref "R11") (pin "2") (pinfunction "2_2") (pintype "passive"))
      (node (ref "U4") (pin "5") (pinfunction "RSENSE-_5") (pintype "bidirectional"))
    )
    (net (code "48") (name "RST") (class "Default")
      (node (ref "C8") (pin "1") (pinfunction "1_1") (pintype "passive"))
      (node (ref "R3") (pin "1") (pinfunction "1_1") (pintype "passive"))
      (node (ref "RST") (pin "TP") (pinfunction "TP_TP") (pintype "input"))
      (node (ref "U3") (pin "29") (pinfunction "PC6(/RESET)_29") (pintype "bidirectional"))
    )
    (net (code "49") (name "RX") (class "Default")
      (node (ref "RX") (pin "TP") (pinfunction "TP_TP") (pintype "input"))
      (node (ref "TTL") (pin "3") (pinfunction "3_3") (pintype "passive"))
      (node (ref "U3") (pin "30") (pinfunction "PD0(RXD)_30") (pintype "bidirectional"))
    )
    (net (code "50") (name "SCK") (class "Default")
      (node (ref "SCK") (pin "TP") (pinfunction "TP_TP") (pintype "input"))
      (node (ref "U3") (pin "17") (pinfunction "PB5(SCK)_17") (pintype "bidirectional"))
    )
    (net (code "51") (name "SIM_CLK") (class "Default")
      (node (ref "R18") (pin "2") (pinfunction "2_2") (pintype "passive"))
      (node (ref "U2") (pin "32") (pinfunction "SIM_CLK_32") (pintype "output"))
    )
    (net (code "52") (name "SIM_CLK_DIRECT") (class "Default")
      (node (ref "R18") (pin "1") (pinfunction "1_1") (pintype "passive"))
      (node (ref "SIMHOLDER") (pin "3") (pinfunction "CLK_3") (pintype "bidirectional"))
      (node (ref "VCC1") (pin "TP") (pinfunction "TP_TP") (pintype "input"))
    )
    (net (code "53") (name "SIM_DATA") (class "Default")
      (node (ref "R19") (pin "1") (pinfunction "1_1") (pintype "passive"))
      (node (ref "U2") (pin "31") (pinfunction "SIM_DATA_31") (pintype "bidirectional"))
    )
    (net (code "54") (name "SIM_DATA_DIRECT") (class "Default")
      (node (ref "GND11") (pin "TP") (pinfunction "TP_TP") (pintype "input"))
      (node (ref "R19") (pin "2") (pinfunction "2_2") (pintype "passive"))
      (node (ref "SIMHOLDER") (pin "4") (pinfunction "I/O_4") (pintype "bidirectional"))
    )
    (net (code "55") (name "SIM_RST") (class "Default")
      (node (ref "R17") (pin "2") (pinfunction "2_2") (pintype "passive"))
      (node (ref "U2") (pin "33") (pinfunction "SIM_RST_33") (pintype "output"))
    )
    (net (code "56") (name "SIM_RST_DIRECT") (class "Default")
      (node (ref "R17") (pin "1") (pinfunction "1_1") (pintype "passive"))
      (node (ref "SCK1") (pin "TP") (pinfunction "TP_TP") (pintype "input"))
      (node (ref "SIMHOLDER") (pin "2") (pinfunction "RST_2") (pintype "bidirectional"))
    )
    (net (code "57") (name "SIM_VDD") (class "Default")
      (node (ref "C20") (pin "1") (pinfunction "1_1") (pintype "passive"))
      (node (ref "RST1") (pin "TP") (pinfunction "TP_TP") (pintype "input"))
      (node (ref "SIMHOLDER") (pin "1") (pinfunction "VCC_1") (pintype "bidirectional"))
      (node (ref "U2") (pin "30") (pinfunction "SIM_VDD_30") (pintype "output"))
    )
    (net (code "58") (name "STATUS") (class "Default")
      (node (ref "R20") (pin "2") (pinfunction "2_2") (pintype "passive"))
      (node (ref "U2") (pin "66") (pinfunction "STATUS_66") (pintype "output"))
      (node (ref "U3") (pin "10") (pinfunction "PD6(AIN0)_10") (pintype "bidirectional"))
    )
    (net (code "59") (name "TX") (class "Default")
      (node (ref "TTL") (pin "2") (pinfunction "2_2") (pintype "passive"))
      (node (ref "TX") (pin "TP") (pinfunction "TP_TP") (pintype "input"))
      (node (ref "U3") (pin "31") (pinfunction "PD1(TXD)_31") (pintype "bidirectional"))
    )
    (net (code "60") (name "VCC") (class "Default")
      (node (ref "C17") (pin "2") (pinfunction "2_2") (pintype "passive"))
      (node (ref "C18") (pin "2") (pinfunction "2_2") (pintype "passive"))
      (node (ref "C19") (pin "2") (pinfunction "2_2") (pintype "passive"))
      (node (ref "C2") (pin "+") (pinfunction "+_+") (pintype "passive"))
      (node (ref "C21") (pin "2") (pinfunction "2_2") (pintype "passive"))
      (node (ref "C22") (pin "2") (pinfunction "2_2") (pintype "passive"))
      (node (ref "C3") (pin "+") (pinfunction "+_+") (pintype "passive"))
      (node (ref "C4") (pin "2") (pinfunction "2_2") (pintype "passive"))
      (node (ref "C5") (pin "2") (pinfunction "2_2") (pintype "passive"))
      (node (ref "C7") (pin "2") (pinfunction "2_2") (pintype "passive"))
      (node (ref "C9") (pin "2") (pinfunction "2_2") (pintype "passive"))
      (node (ref "L1") (pin "2") (pinfunction "2_2") (pintype "passive"))
      (node (ref "NETLIGHT") (pin "+") (pinfunction "+_+") (pintype "passive"))
      (node (ref "POWER") (pin "+") (pinfunction "+_+") (pintype "passive"))
      (node (ref "R3") (pin "2") (pinfunction "2_2") (pintype "passive"))
      (node (ref "R6") (pin "2") (pinfunction "2_2") (pintype "passive"))
      (node (ref "STATUS") (pin "+") (pinfunction "+_+") (pintype "passive"))
      (node (ref "TTL") (pin "4") (pinfunction "4_4") (pintype "passive"))
      (node (ref "U2") (pin "55") (pinfunction "VBAT_55") (pintype "power_in"))
      (node (ref "U2") (pin "56") (pinfunction "VBAT_56") (pintype "power_in"))
      (node (ref "U2") (pin "57") (pinfunction "VBAT_57") (pintype "power_in"))
      (node (ref "U3") (pin "18") (pinfunction "AVCC_18") (pintype "bidirectional"))
      (node (ref "U3") (pin "20") (pinfunction "AREF_20") (pintype "bidirectional"))
      (node (ref "U3") (pin "4") (pinfunction "VCC_4") (pintype "bidirectional"))
      (node (ref "U3") (pin "6") (pinfunction "VCC_6") (pintype "bidirectional"))
      (node (ref "VCC") (pin "TP") (pinfunction "TP_TP") (pintype "input"))
    )
    (net (code "61") (name "VDD") (class "Default")
      (node (ref "C11") (pin "2") (pinfunction "2_2") (pintype "passive"))
      (node (ref "C24") (pin "2") (pinfunction "2_2") (pintype "passive"))
      (node (ref "D2") (pin "C") (pinfunction "C_C") (pintype "passive"))
      (node (ref "R4") (pin "2") (pinfunction "2_2") (pintype "passive"))
      (node (ref "U1") (pin "2") (pinfunction "VIN_2") (pintype "input"))
    )
    (net (code "62") (name "VRTC") (class "Default")
      (node (ref "C15") (pin "+") (pinfunction "+_+") (pintype "passive"))
      (node (ref "U2") (pin "26") (pinfunction "VRTC_26") (pintype "bidirectional"))
    )
    (net (code "63") (name "unconnected-(SIMHOLDER-VPP-Pad5)") (class "Default")
      (node (ref "SIMHOLDER") (pin "5") (pinfunction "VPP_5") (pintype "bidirectional"))
    )
    (net (code "64") (name "unconnected-(U1-NC-Pad1)") (class "Default")
      (node (ref "U1") (pin "1") (pinfunction "NC_1") (pintype "no_connect"))
    )
    (net (code "65") (name "unconnected-(U1-NC-Pad6)") (class "Default")
      (node (ref "U1") (pin "6") (pinfunction "NC_6") (pintype "no_connect"))
    )
    (net (code "66") (name "unconnected-(U1-NC-Pad8)") (class "Default")
      (node (ref "U1") (pin "8") (pinfunction "NC_8") (pintype "no_connect"))
    )
    (net (code "67") (name "unconnected-(U2-ADC-Pad25)") (class "Default")
      (node (ref "U2") (pin "25") (pinfunction "ADC_25") (pintype "input"))
    )
    (net (code "68") (name "unconnected-(U2-CTS-Pad7)") (class "Default")
      (node (ref "U2") (pin "7") (pinfunction "CTS_7") (pintype "output"))
    )
    (net (code "69") (name "unconnected-(U2-DBG_RXD-Pad28)") (class "Default")
      (node (ref "U2") (pin "28") (pinfunction "DBG_RXD_28") (pintype "input"))
    )
    (net (code "70") (name "unconnected-(U2-DBG_TXD-Pad27)") (class "Default")
      (node (ref "U2") (pin "27") (pinfunction "DBG_TXD_27") (pintype "output"))
    )
    (net (code "71") (name "unconnected-(U2-DCD-Pad5)") (class "Default")
      (node (ref "U2") (pin "5") (pinfunction "DCD_5") (pintype "output"))
    )
    (net (code "72") (name "unconnected-(U2-DISP_CLK-Pad11)") (class "Default")
      (node (ref "U2") (pin "11") (pinfunction "DISP_CLK_11") (pintype "output"))
    )
    (net (code "73") (name "unconnected-(U2-DISP_CS-Pad14)") (class "Default")
      (node (ref "U2") (pin "14") (pinfunction "DISP_CS_14") (pintype "output"))
    )
    (net (code "74") (name "unconnected-(U2-DISP_DATA-Pad12)") (class "Default")
      (node (ref "U2") (pin "12") (pinfunction "DISP_DATA_12") (pintype "bidirectional"))
    )
    (net (code "75") (name "unconnected-(U2-DISP_D{slash}C-Pad13)") (class "Default")
      (node (ref "U2") (pin "13") (pinfunction "DISP_D/C_13") (pintype "output"))
    )
    (net (code "76") (name "unconnected-(U2-DSR-Pad6)") (class "Default")
      (node (ref "U2") (pin "6") (pinfunction "DSR_6") (pintype "output"))
    )
    (net (code "77") (name "unconnected-(U2-DTR-Pad3)") (class "Default")
      (node (ref "U2") (pin "3") (pinfunction "DTR_3") (pintype "input"))
    )
    (net (code "78") (name "unconnected-(U2-GPIO1{slash}KBR4-Pad40)") (class "Default")
      (node (ref "U2") (pin "40") (pinfunction "GPIO1/KBR4_40") (pintype "output"))
    )
    (net (code "79") (name "unconnected-(U2-GPIO2{slash}KBR3-Pad41)") (class "Default")
      (node (ref "U2") (pin "41") (pinfunction "GPIO2/KBR3_41") (pintype "output"))
    )
    (net (code "80") (name "unconnected-(U2-GPIO3{slash}KBR2-Pad42)") (class "Default")
      (node (ref "U2") (pin "42") (pinfunction "GPIO3/KBR2_42") (pintype "output"))
    )
    (net (code "81") (name "unconnected-(U2-GPIO4{slash}KBR1-Pad43)") (class "Default")
      (node (ref "U2") (pin "43") (pinfunction "GPIO4/KBR1_43") (pintype "output"))
    )
    (net (code "82") (name "unconnected-(U2-GPIO5{slash}KBR0-Pad44)") (class "Default")
      (node (ref "U2") (pin "44") (pinfunction "GPIO5/KBR0_44") (pintype "output"))
    )
    (net (code "83") (name "unconnected-(U2-GPIO6{slash}KBC4-Pad47)") (class "Default")
      (node (ref "U2") (pin "47") (pinfunction "GPIO6/KBC4_47") (pintype "input"))
    )
    (net (code "84") (name "unconnected-(U2-GPIO7{slash}KBC3-Pad48)") (class "Default")
      (node (ref "U2") (pin "48") (pinfunction "GPIO7/KBC3_48") (pintype "bidirectional"))
    )
    (net (code "85") (name "unconnected-(U2-GPIO8{slash}KBC2-Pad49)") (class "Default")
      (node (ref "U2") (pin "49") (pinfunction "GPIO8/KBC2_49") (pintype "input"))
    )
    (net (code "86") (name "unconnected-(U2-GPIO9{slash}KBC1-Pad50)") (class "Default")
      (node (ref "U2") (pin "50") (pinfunction "GPIO9/KBC1_50") (pintype "input"))
    )
    (net (code "87") (name "unconnected-(U2-GPIO10{slash}KBC0-Pad51)") (class "Default")
      (node (ref "U2") (pin "51") (pinfunction "GPIO10/KBC0_51") (pintype "bidirectional"))
    )
    (net (code "88") (name "unconnected-(U2-GPIO11-Pad67)") (class "Default")
      (node (ref "U2") (pin "67") (pinfunction "GPIO11_67") (pintype "bidirectional"))
    )
    (net (code "89") (name "unconnected-(U2-GPIO12-Pad68)") (class "Default")
      (node (ref "U2") (pin "68") (pinfunction "GPIO12_68") (pintype "bidirectional"))
    )
    (net (code "90") (name "unconnected-(U2-LINEIN_L-Pad24)") (class "Default")
      (node (ref "U2") (pin "24") (pinfunction "LINEIN_L_24") (pintype "input"))
    )
    (net (code "91") (name "unconnected-(U2-LINEIN_R-Pad23)") (class "Default")
      (node (ref "U2") (pin "23") (pinfunction "LINEIN_R_23") (pintype "input"))
    )
    (net (code "92") (name "unconnected-(U2-MIC_N-Pad20)") (class "Default")
      (node (ref "U2") (pin "20") (pinfunction "MIC_N_20") (pintype "input"))
    )
    (net (code "93") (name "unconnected-(U2-MIC_P-Pad19)") (class "Default")
      (node (ref "U2") (pin "19") (pinfunction "MIC_P_19") (pintype "input"))
    )
    (net (code "94") (name "unconnected-(U2-NRESET-Pad16)") (class "Default")
      (node (ref "U2") (pin "16") (pinfunction "NRESET_16") (pintype "input"))
    )
    (net (code "95") (name "unconnected-(U2-PWM1-Pad35)") (class "Default")
      (node (ref "U2") (pin "35") (pinfunction "PWM1_35") (pintype "output"))
    )
    (net (code "96") (name "unconnected-(U2-PWM2-Pad36)") (class "Default")
      (node (ref "U2") (pin "36") (pinfunction "PWM2_36") (pintype "output"))
    )
    (net (code "97") (name "unconnected-(U2-PWRKEY_OUT-Pad2)") (class "Default")
      (node (ref "U2") (pin "2") (pinfunction "PWRKEY_OUT_2") (pintype "output"))
    )
    (net (code "98") (name "unconnected-(U2-RI-Pad4)") (class "Default")
      (node (ref "U2") (pin "4") (pinfunction "RI_4") (pintype "output"))
    )
    (net (code "99") (name "unconnected-(U2-RTS-Pad8)") (class "Default")
      (node (ref "U2") (pin "8") (pinfunction "RTS_8") (pintype "input"))
    )
    (net (code "100") (name "unconnected-(U2-SCL-Pad38)") (class "Default")
      (node (ref "U2") (pin "38") (pinfunction "SCL_38") (pintype "output"))
    )
    (net (code "101") (name "unconnected-(U2-SDA-Pad37)") (class "Default")
      (node (ref "U2") (pin "37") (pinfunction "SDA_37") (pintype "bidirectional"))
    )
    (net (code "102") (name "unconnected-(U2-SIM_PRESENCE-Pad34)") (class "Default")
      (node (ref "U2") (pin "34") (pinfunction "SIM_PRESENCE_34") (pintype "input"))
    )
    (net (code "103") (name "unconnected-(U2-SPK_N-Pad22)") (class "Default")
      (node (ref "U2") (pin "22") (pinfunction "SPK_N_22") (pintype "output"))
    )
    (net (code "104") (name "unconnected-(U2-SPK_P-Pad21)") (class "Default")
      (node (ref "U2") (pin "21") (pinfunction "SPK_P_21") (pintype "output"))
    )
    (net (code "105") (name "unconnected-(U2-VDD_EXT-Pad15)") (class "Default")
      (node (ref "U2") (pin "15") (pinfunction "VDD_EXT_15") (pintype "output"))
    )
    (net (code "106") (name "unconnected-(U3-ADC6-Pad19)") (class "Default")
      (node (ref "U3") (pin "19") (pinfunction "ADC6_19") (pintype "bidirectional"))
    )
    (net (code "107") (name "unconnected-(U3-ADC7-Pad22)") (class "Default")
      (node (ref "U3") (pin "22") (pinfunction "ADC7_22") (pintype "bidirectional"))
    )
    (net (code "108") (name "unconnected-(U3-PB0(ICP)-Pad12)") (class "Default")
      (node (ref "U3") (pin "12") (pinfunction "PB0(ICP)_12") (pintype "bidirectional"))
    )
    (net (code "109") (name "unconnected-(U3-PB1(OC1A)-Pad13)") (class "Default")
      (node (ref "U3") (pin "13") (pinfunction "PB1(OC1A)_13") (pintype "bidirectional"))
    )
  )
)
